# Sch.net
KiCad netlist of a schematic drawn in EAGLE
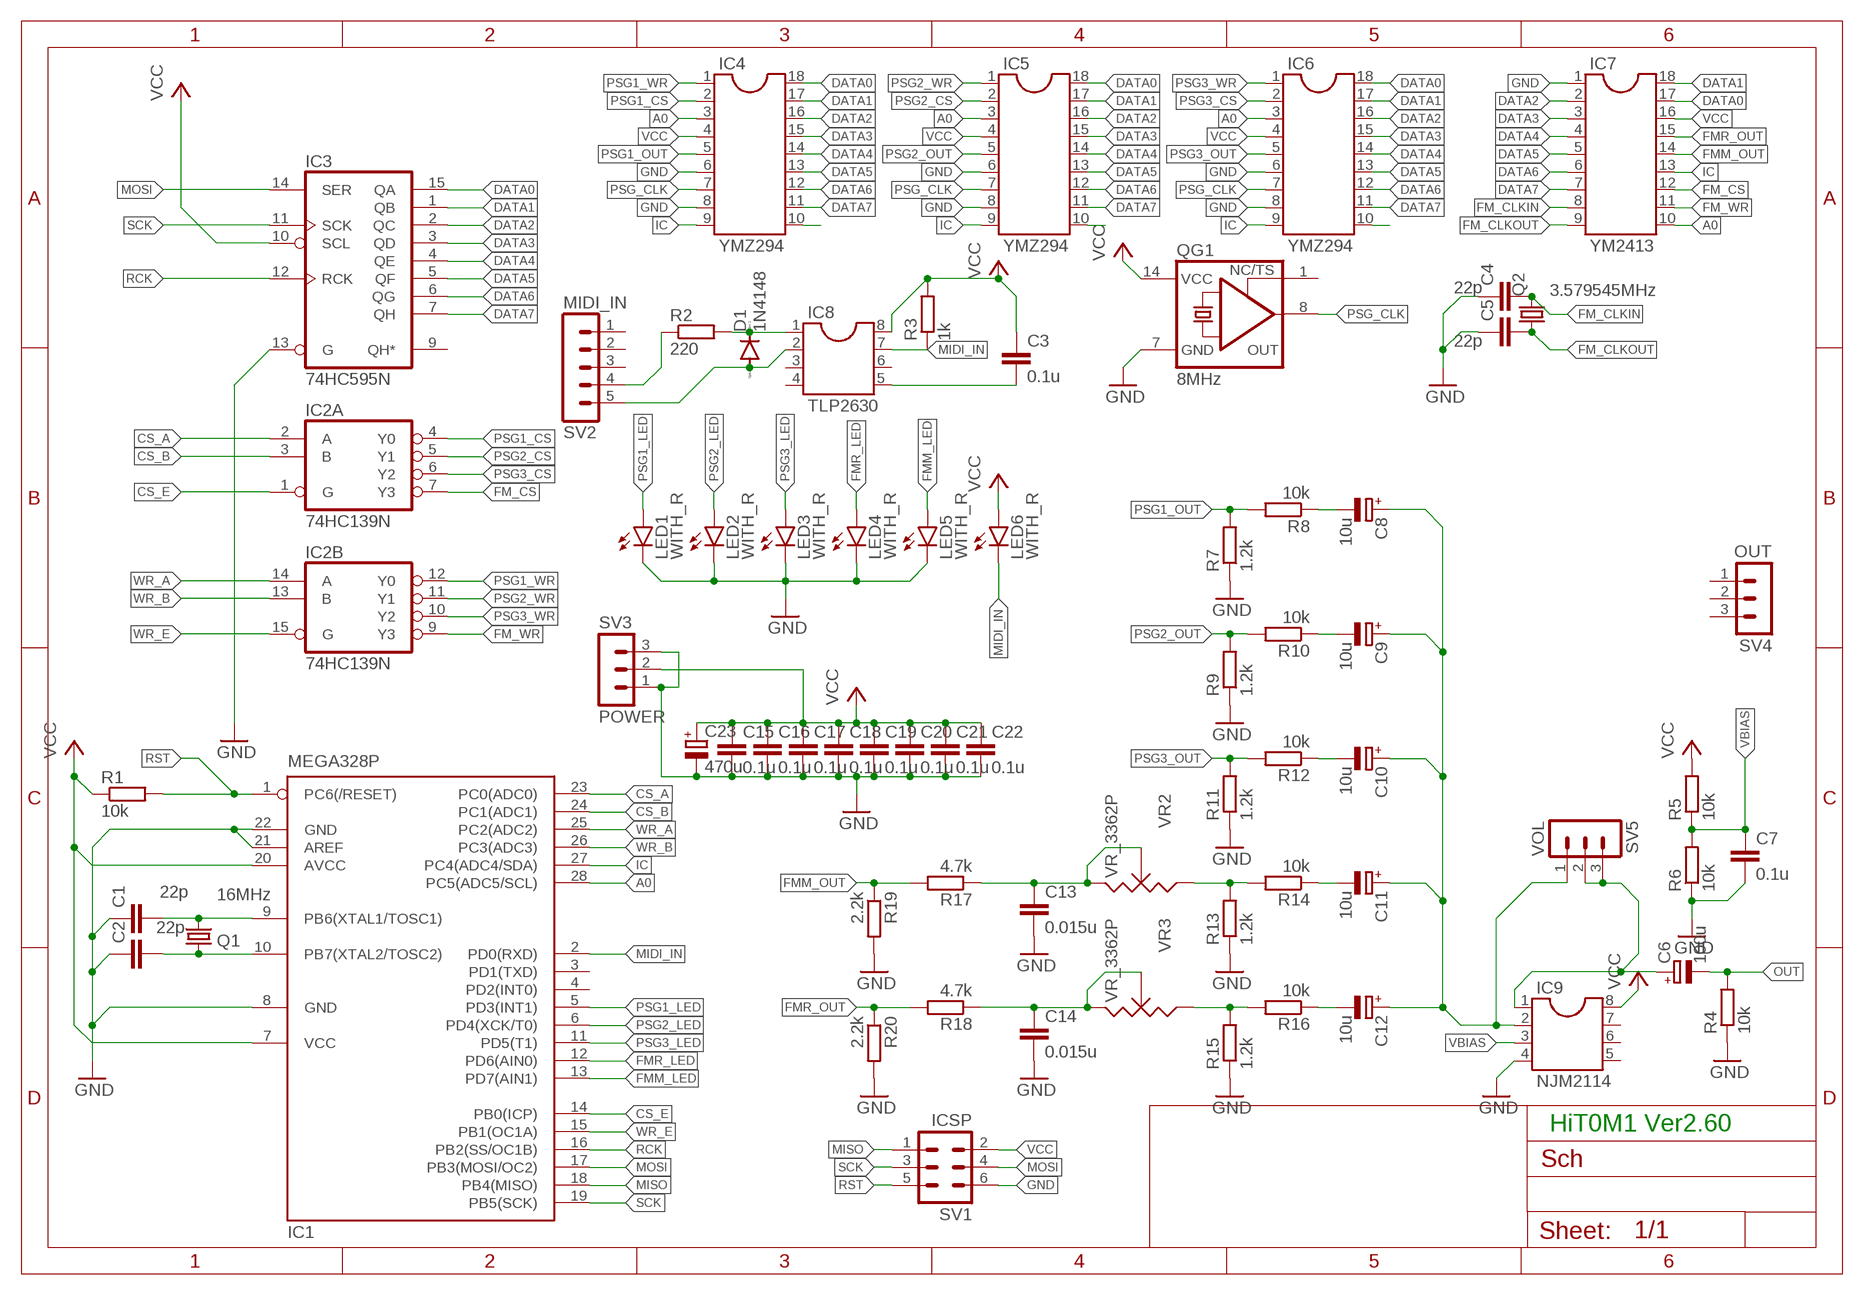
[diagram p0: schematic, sheet 1]

(export (version "E")
  (design (tool "Eeschema 10.0.6"))
  (components
    (comp (ref "C1")
      (value "22p")
      (footprint "eagle-import:C025-025X050")
      (libsource (lib "eagle-import") (part "C-EU025-025X050"))
    )
    (comp (ref "C2")
      (value "22p")
      (footprint "eagle-import:C025-025X050")
      (libsource (lib "eagle-import") (part "C-EU025-025X050"))
    )
    (comp (ref "C3")
      (value "0.1u")
      (footprint "eagle-import:C025-025X050")
      (libsource (lib "eagle-import") (part "C-EU025-025X050"))
    )
    (comp (ref "C4")
      (value "22p")
      (footprint "eagle-import:C025-025X050")
      (libsource (lib "eagle-import") (part "C-EU025-025X050"))
    )
    (comp (ref "C5")
      (value "22p")
      (footprint "eagle-import:C025-025X050")
      (libsource (lib "eagle-import") (part "C-EU025-025X050"))
    )
    (comp (ref "C6")
      (value "100u")
      (footprint "eagle-import:E2,5-6")
      (libsource (lib "eagle-import") (part "CPOL-EUE2.5-6"))
    )
    (comp (ref "C7")
      (value "0.1u")
      (footprint "eagle-import:C025-025X050")
      (libsource (lib "eagle-import") (part "C-EU025-025X050"))
    )
    (comp (ref "C8")
      (value "10u")
      (footprint "eagle-import:E2,5-6")
      (libsource (lib "eagle-import") (part "CPOL-EUE2.5-6"))
    )
    (comp (ref "C9")
      (value "10u")
      (footprint "eagle-import:E2,5-6")
      (libsource (lib "eagle-import") (part "CPOL-EUE2.5-6"))
    )
    (comp (ref "C10")
      (value "10u")
      (footprint "eagle-import:E2,5-6")
      (libsource (lib "eagle-import") (part "CPOL-EUE2.5-6"))
    )
    (comp (ref "C11")
      (value "10u")
      (footprint "eagle-import:E2,5-6")
      (libsource (lib "eagle-import") (part "CPOL-EUE2.5-6"))
    )
    (comp (ref "C12")
      (value "10u")
      (footprint "eagle-import:E2,5-6")
      (libsource (lib "eagle-import") (part "CPOL-EUE2.5-6"))
    )
    (comp (ref "C13")
      (value "0.015u")
      (footprint "eagle-import:C050-025X075")
      (libsource (lib "eagle-import") (part "C-EU050-025X075"))
    )
    (comp (ref "C14")
      (value "0.015u")
      (footprint "eagle-import:C050-025X075")
      (libsource (lib "eagle-import") (part "C-EU050-025X075"))
    )
    (comp (ref "C15")
      (value "0.1u")
      (footprint "eagle-import:C025-025X050")
      (libsource (lib "eagle-import") (part "C-EU025-025X050"))
    )
    (comp (ref "C16")
      (value "0.1u")
      (footprint "eagle-import:C025-025X050")
      (libsource (lib "eagle-import") (part "C-EU025-025X050"))
    )
    (comp (ref "C17")
      (value "0.1u")
      (footprint "eagle-import:C025-025X050")
      (libsource (lib "eagle-import") (part "C-EU025-025X050"))
    )
    (comp (ref "C18")
      (value "0.1u")
      (footprint "eagle-import:C025-025X050")
      (libsource (lib "eagle-import") (part "C-EU025-025X050"))
    )
    (comp (ref "C19")
      (value "0.1u")
      (footprint "eagle-import:C025-025X050")
      (libsource (lib "eagle-import") (part "C-EU025-025X050"))
    )
    (comp (ref "C20")
      (value "0.1u")
      (footprint "eagle-import:C025-025X050")
      (libsource (lib "eagle-import") (part "C-EU025-025X050"))
    )
    (comp (ref "C21")
      (value "0.1u")
      (footprint "eagle-import:C025-025X050")
      (libsource (lib "eagle-import") (part "C-EU025-025X050"))
    )
    (comp (ref "C22")
      (value "0.1u")
      (footprint "eagle-import:C025-025X050")
      (libsource (lib "eagle-import") (part "C-EU025-025X050"))
    )
    (comp (ref "C23")
      (value "470u")
      (footprint "eagle-import:E2,5-6")
      (libsource (lib "eagle-import") (part "CPOL-EUE2.5-6"))
    )
    (comp (ref "D1")
      (value "1N4148")
      (footprint "eagle-import:DO35-7")
      (libsource (lib "eagle-import") (part "1N4148DO35-7"))
    )
    (comp (ref "IC1")
      (value "MEGA328P")
      (footprint "eagle-import:DIL28-3")
      (libsource (lib "eagle-import") (part "MEGA8-P"))
    )
    (comp (ref "IC2")
      (value "74HC139N")
      (footprint "eagle-import:DIL16")
      (libsource (lib "eagle-import") (part "74139NHC"))
    )
    (comp (ref "IC3")
      (value "74HC595N")
      (footprint "eagle-import:DIL16")
      (libsource (lib "eagle-import") (part "74595NHC"))
    )
    (comp (ref "IC4")
      (value "YMZ294")
      (footprint "eagle-import:SOCKET-18")
      (libsource (lib "eagle-import") (part "DIL18S"))
    )
    (comp (ref "IC5")
      (value "YMZ294")
      (footprint "eagle-import:SOCKET-18")
      (libsource (lib "eagle-import") (part "DIL18S"))
    )
    (comp (ref "IC6")
      (value "YMZ294")
      (footprint "eagle-import:SOCKET-18")
      (libsource (lib "eagle-import") (part "DIL18S"))
    )
    (comp (ref "IC7")
      (value "YM2413")
      (footprint "eagle-import:SOCKET-18")
      (libsource (lib "eagle-import") (part "DIL18S"))
    )
    (comp (ref "IC8")
      (value "TLP2630")
      (footprint "eagle-import:SOCKET-08")
      (libsource (lib "eagle-import") (part "DIL8S"))
    )
    (comp (ref "IC9")
      (value "NJM2114")
      (footprint "eagle-import:SOCKET-08")
      (libsource (lib "eagle-import") (part "DIL8S"))
    )
    (comp (ref "LED1")
      (value "WITH_R")
      (footprint "eagle-import:LED3MM")
      (libsource (lib "eagle-import") (part "LED3MM"))
    )
    (comp (ref "LED2")
      (value "WITH_R")
      (footprint "eagle-import:LED3MM")
      (libsource (lib "eagle-import") (part "LED3MM"))
    )
    (comp (ref "LED3")
      (value "WITH_R")
      (footprint "eagle-import:LED3MM")
      (libsource (lib "eagle-import") (part "LED3MM"))
    )
    (comp (ref "LED4")
      (value "WITH_R")
      (footprint "eagle-import:LED3MM")
      (libsource (lib "eagle-import") (part "LED3MM"))
    )
    (comp (ref "LED5")
      (value "WITH_R")
      (footprint "eagle-import:LED3MM")
      (libsource (lib "eagle-import") (part "LED3MM"))
    )
    (comp (ref "LED6")
      (value "WITH_R")
      (footprint "eagle-import:LED3MM")
      (libsource (lib "eagle-import") (part "LED3MM"))
    )
    (comp (ref "Q1")
      (value "16MHz")
      (footprint "eagle-import:HC49_S")
      (libsource (lib "eagle-import") (part "CRYSTALHC49S"))
    )
    (comp (ref "Q2")
      (value "3.579545MHz")
      (footprint "eagle-import:HC49_S")
      (libsource (lib "eagle-import") (part "CRYSTALHC49S"))
    )
    (comp (ref "QG1")
      (value "8MHz")
      (footprint "eagle-import:DIL14S")
      (libsource (lib "eagle-import") (part "XO-14"))
    )
    (comp (ref "R1")
      (value "10k")
      (footprint "eagle-import:0207_10")
      (libsource (lib "eagle-import") (part "R-EU_0207/10"))
    )
    (comp (ref "R2")
      (value "220")
      (footprint "eagle-import:0207_10")
      (libsource (lib "eagle-import") (part "R-EU_0207/10"))
    )
    (comp (ref "R3")
      (value "1k")
      (footprint "eagle-import:0207_10")
      (libsource (lib "eagle-import") (part "R-EU_0207/10"))
    )
    (comp (ref "R4")
      (value "10k")
      (footprint "eagle-import:0207_10")
      (libsource (lib "eagle-import") (part "R-EU_0207/10"))
    )
    (comp (ref "R5")
      (value "10k")
      (footprint "eagle-import:0207_10")
      (libsource (lib "eagle-import") (part "R-EU_0207/10"))
    )
    (comp (ref "R6")
      (value "10k")
      (footprint "eagle-import:0207_10")
      (libsource (lib "eagle-import") (part "R-EU_0207/10"))
    )
    (comp (ref "R7")
      (value "1.2k")
      (footprint "eagle-import:0207_2V")
      (libsource (lib "eagle-import") (part "R-EU_0207/2V"))
    )
    (comp (ref "R8")
      (value "10k")
      (footprint "eagle-import:0207_2V")
      (libsource (lib "eagle-import") (part "R-EU_0207/2V"))
    )
    (comp (ref "R9")
      (value "1.2k")
      (footprint "eagle-import:0207_2V")
      (libsource (lib "eagle-import") (part "R-EU_0207/2V"))
    )
    (comp (ref "R10")
      (value "10k")
      (footprint "eagle-import:0207_2V")
      (libsource (lib "eagle-import") (part "R-EU_0207/2V"))
    )
    (comp (ref "R11")
      (value "1.2k")
      (footprint "eagle-import:0207_2V")
      (libsource (lib "eagle-import") (part "R-EU_0207/2V"))
    )
    (comp (ref "R12")
      (value "10k")
      (footprint "eagle-import:0207_2V")
      (libsource (lib "eagle-import") (part "R-EU_0207/2V"))
    )
    (comp (ref "R13")
      (value "1.2k")
      (footprint "eagle-import:0207_2V")
      (libsource (lib "eagle-import") (part "R-EU_0207/2V"))
    )
    (comp (ref "R14")
      (value "10k")
      (footprint "eagle-import:0207_2V")
      (libsource (lib "eagle-import") (part "R-EU_0207/2V"))
    )
    (comp (ref "R15")
      (value "1.2k")
      (footprint "eagle-import:0207_2V")
      (libsource (lib "eagle-import") (part "R-EU_0207/2V"))
    )
    (comp (ref "R16")
      (value "10k")
      (footprint "eagle-import:0207_2V")
      (libsource (lib "eagle-import") (part "R-EU_0207/2V"))
    )
    (comp (ref "R17")
      (value "4.7k")
      (footprint "eagle-import:0207_2V")
      (libsource (lib "eagle-import") (part "R-EU_0207/2V"))
    )
    (comp (ref "R18")
      (value "4.7k")
      (footprint "eagle-import:0207_2V")
      (libsource (lib "eagle-import") (part "R-EU_0207/2V"))
    )
    (comp (ref "R19")
      (value "2.2k")
      (footprint "eagle-import:0207_2V")
      (libsource (lib "eagle-import") (part "R-EU_0207/2V"))
    )
    (comp (ref "R20")
      (value "2.2k")
      (footprint "eagle-import:0207_2V")
      (libsource (lib "eagle-import") (part "R-EU_0207/2V"))
    )
    (comp (ref "SV1")
      (value "ICSP")
      (footprint "eagle-import:MA03-2")
      (libsource (lib "eagle-import") (part "MA03-2"))
    )
    (comp (ref "SV2")
      (value "MIDI_IN")
      (footprint "eagle-import:MA05-1")
      (libsource (lib "eagle-import") (part "MA05-1"))
    )
    (comp (ref "SV3")
      (value "POWER")
      (footprint "eagle-import:MA03-1")
      (libsource (lib "eagle-import") (part "MA03-1"))
    )
    (comp (ref "SV4")
      (value "OUT")
      (footprint "eagle-import:MA03-1")
      (libsource (lib "eagle-import") (part "MA03-1"))
    )
    (comp (ref "SV5")
      (value "VOL")
      (footprint "eagle-import:MA03-1")
      (libsource (lib "eagle-import") (part "MA03-1"))
    )
    (comp (ref "VR2")
      (value "VR_3362P")
      (footprint "eagle-import:VR_3362P")
      (libsource (lib "eagle-import") (part "P-03277_VR_3362P"))
    )
    (comp (ref "VR3")
      (value "VR_3362P")
      (footprint "eagle-import:VR_3362P")
      (libsource (lib "eagle-import") (part "P-03277_VR_3362P"))
    )
  )
  (nets
    (net (code "1") (name "A0") (class "Default")
      (node (ref "IC1") (pin "28") (pinfunction "PC5(ADC5/SCL)_28") (pintype "bidirectional"))
      (node (ref "IC4") (pin "3") (pinfunction "3_3") (pintype "passive"))
      (node (ref "IC5") (pin "3") (pinfunction "3_3") (pintype "passive"))
      (node (ref "IC6") (pin "3") (pinfunction "3_3") (pintype "passive"))
      (node (ref "IC7") (pin "10") (pinfunction "10_10") (pintype "passive"))
    )
    (net (code "2") (name "CS_A") (class "Default")
      (node (ref "IC1") (pin "23") (pinfunction "PC0(ADC0)_23") (pintype "bidirectional"))
      (node (ref "IC2") (pin "2") (pinfunction "A_2") (pintype "input"))
    )
    (net (code "3") (name "CS_B") (class "Default")
      (node (ref "IC1") (pin "24") (pinfunction "PC1(ADC1)_24") (pintype "bidirectional"))
      (node (ref "IC2") (pin "3") (pinfunction "B_3") (pintype "input"))
    )
    (net (code "4") (name "CS_E") (class "Default")
      (node (ref "IC1") (pin "14") (pinfunction "PB0(ICP)_14") (pintype "bidirectional"))
      (node (ref "IC2") (pin "1") (pinfunction "G_1") (pintype "input"))
    )
    (net (code "5") (name "DATA0") (class "Default")
      (node (ref "IC3") (pin "15") (pinfunction "QA_15") (pintype "tri_state"))
      (node (ref "IC4") (pin "18") (pinfunction "18_18") (pintype "passive"))
      (node (ref "IC5") (pin "18") (pinfunction "18_18") (pintype "passive"))
      (node (ref "IC6") (pin "18") (pinfunction "18_18") (pintype "passive"))
      (node (ref "IC7") (pin "17") (pinfunction "17_17") (pintype "passive"))
    )
    (net (code "6") (name "DATA1") (class "Default")
      (node (ref "IC3") (pin "1") (pinfunction "QB_1") (pintype "tri_state"))
      (node (ref "IC4") (pin "17") (pinfunction "17_17") (pintype "passive"))
      (node (ref "IC5") (pin "17") (pinfunction "17_17") (pintype "passive"))
      (node (ref "IC6") (pin "17") (pinfunction "17_17") (pintype "passive"))
      (node (ref "IC7") (pin "18") (pinfunction "18_18") (pintype "passive"))
    )
    (net (code "7") (name "DATA2") (class "Default")
      (node (ref "IC3") (pin "2") (pinfunction "QC_2") (pintype "tri_state"))
      (node (ref "IC4") (pin "16") (pinfunction "16_16") (pintype "passive"))
      (node (ref "IC5") (pin "16") (pinfunction "16_16") (pintype "passive"))
      (node (ref "IC6") (pin "16") (pinfunction "16_16") (pintype "passive"))
      (node (ref "IC7") (pin "2") (pinfunction "2_2") (pintype "passive"))
    )
    (net (code "8") (name "DATA3") (class "Default")
      (node (ref "IC3") (pin "3") (pinfunction "QD_3") (pintype "tri_state"))
      (node (ref "IC4") (pin "15") (pinfunction "15_15") (pintype "passive"))
      (node (ref "IC5") (pin "15") (pinfunction "15_15") (pintype "passive"))
      (node (ref "IC6") (pin "15") (pinfunction "15_15") (pintype "passive"))
      (node (ref "IC7") (pin "3") (pinfunction "3_3") (pintype "passive"))
    )
    (net (code "9") (name "DATA4") (class "Default")
      (node (ref "IC3") (pin "4") (pinfunction "QE_4") (pintype "tri_state"))
      (node (ref "IC4") (pin "14") (pinfunction "14_14") (pintype "passive"))
      (node (ref "IC5") (pin "14") (pinfunction "14_14") (pintype "passive"))
      (node (ref "IC6") (pin "14") (pinfunction "14_14") (pintype "passive"))
      (node (ref "IC7") (pin "4") (pinfunction "4_4") (pintype "passive"))
    )
    (net (code "10") (name "DATA5") (class "Default")
      (node (ref "IC3") (pin "5") (pinfunction "QF_5") (pintype "tri_state"))
      (node (ref "IC4") (pin "13") (pinfunction "13_13") (pintype "passive"))
      (node (ref "IC5") (pin "13") (pinfunction "13_13") (pintype "passive"))
      (node (ref "IC6") (pin "13") (pinfunction "13_13") (pintype "passive"))
      (node (ref "IC7") (pin "5") (pinfunction "5_5") (pintype "passive"))
    )
    (net (code "11") (name "DATA6") (class "Default")
      (node (ref "IC3") (pin "6") (pinfunction "QG_6") (pintype "tri_state"))
      (node (ref "IC4") (pin "12") (pinfunction "12_12") (pintype "passive"))
      (node (ref "IC5") (pin "12") (pinfunction "12_12") (pintype "passive"))
      (node (ref "IC6") (pin "12") (pinfunction "12_12") (pintype "passive"))
      (node (ref "IC7") (pin "6") (pinfunction "6_6") (pintype "passive"))
    )
    (net (code "12") (name "DATA7") (class "Default")
      (node (ref "IC3") (pin "7") (pinfunction "QH_7") (pintype "tri_state"))
      (node (ref "IC4") (pin "11") (pinfunction "11_11") (pintype "passive"))
      (node (ref "IC5") (pin "11") (pinfunction "11_11") (pintype "passive"))
      (node (ref "IC6") (pin "11") (pinfunction "11_11") (pintype "passive"))
      (node (ref "IC7") (pin "7") (pinfunction "7_7") (pintype "passive"))
    )
    (net (code "13") (name "FMM_LED") (class "Default")
      (node (ref "IC1") (pin "13") (pinfunction "PD7(AIN1)_13") (pintype "bidirectional"))
      (node (ref "LED5") (pin "A") (pinfunction "A_A") (pintype "passive"))
    )
    (net (code "14") (name "FMM_OUT") (class "Default")
      (node (ref "IC7") (pin "14") (pinfunction "14_14") (pintype "passive"))
      (node (ref "R17") (pin "2") (pinfunction "2_2") (pintype "passive"))
      (node (ref "R19") (pin "1") (pinfunction "1_1") (pintype "passive"))
    )
    (net (code "15") (name "FMR_LED") (class "Default")
      (node (ref "IC1") (pin "12") (pinfunction "PD6(AIN0)_12") (pintype "bidirectional"))
      (node (ref "LED4") (pin "A") (pinfunction "A_A") (pintype "passive"))
    )
    (net (code "16") (name "FMR_OUT") (class "Default")
      (node (ref "IC7") (pin "15") (pinfunction "15_15") (pintype "passive"))
      (node (ref "R18") (pin "2") (pinfunction "2_2") (pintype "passive"))
      (node (ref "R20") (pin "1") (pinfunction "1_1") (pintype "passive"))
    )
    (net (code "17") (name "FM_CLKIN") (class "Default")
      (node (ref "C4") (pin "2") (pinfunction "2_2") (pintype "passive"))
      (node (ref "IC7") (pin "8") (pinfunction "8_8") (pintype "passive"))
      (node (ref "Q2") (pin "2") (pinfunction "2_2") (pintype "passive"))
    )
    (net (code "18") (name "FM_CLKOUT") (class "Default")
      (node (ref "C5") (pin "2") (pinfunction "2_2") (pintype "passive"))
      (node (ref "IC7") (pin "9") (pinfunction "9_9") (pintype "passive"))
      (node (ref "Q2") (pin "1") (pinfunction "1_1") (pintype "passive"))
    )
    (net (code "19") (name "FM_CS") (class "Default")
      (node (ref "IC2") (pin "7") (pinfunction "Y3_7") (pintype "output"))
      (node (ref "IC7") (pin "12") (pinfunction "12_12") (pintype "passive"))
    )
    (net (code "20") (name "FM_WR") (class "Default")
      (node (ref "IC2") (pin "9") (pinfunction "Y3_9") (pintype "output"))
      (node (ref "IC7") (pin "11") (pinfunction "11_11") (pintype "passive"))
    )
    (net (code "21") (name "GND") (class "Default")
      (node (ref "C1") (pin "1") (pinfunction "1_1") (pintype "passive"))
      (node (ref "C13") (pin "2") (pinfunction "2_2") (pintype "passive"))
      (node (ref "C14") (pin "2") (pinfunction "2_2") (pintype "passive"))
      (node (ref "C15") (pin "2") (pinfunction "2_2") (pintype "passive"))
      (node (ref "C16") (pin "2") (pinfunction "2_2") (pintype "passive"))
      (node (ref "C17") (pin "2") (pinfunction "2_2") (pintype "passive"))
      (node (ref "C18") (pin "2") (pinfunction "2_2") (pintype "passive"))
      (node (ref "C19") (pin "2") (pinfunction "2_2") (pintype "passive"))
      (node (ref "C2") (pin "1") (pinfunction "1_1") (pintype "passive"))
      (node (ref "C20") (pin "2") (pinfunction "2_2") (pintype "passive"))
      (node (ref "C21") (pin "2") (pinfunction "2_2") (pintype "passive"))
      (node (ref "C22") (pin "2") (pinfunction "2_2") (pintype "passive"))
      (node (ref "C23") (pin "-") (pinfunction "-_-") (pintype "passive"))
      (node (ref "C4") (pin "1") (pinfunction "1_1") (pintype "passive"))
      (node (ref "C5") (pin "1") (pinfunction "1_1") (pintype "passive"))
      (node (ref "C7") (pin "2") (pinfunction "2_2") (pintype "passive"))
      (node (ref "IC1") (pin "21") (pinfunction "AREF_21") (pintype "passive"))
      (node (ref "IC1") (pin "22") (pinfunction "GND_22") (pintype "power_in"))
      (node (ref "IC1") (pin "8") (pinfunction "GND_8") (pintype "power_in"))
      (node (ref "IC3") (pin "13") (pinfunction "G_13") (pintype "input"))
      (node (ref "IC4") (pin "6") (pinfunction "6_6") (pintype "passive"))
      (node (ref "IC4") (pin "8") (pinfunction "8_8") (pintype "passive"))
      (node (ref "IC5") (pin "6") (pinfunction "6_6") (pintype "passive"))
      (node (ref "IC5") (pin "8") (pinfunction "8_8") (pintype "passive"))
      (node (ref "IC6") (pin "6") (pinfunction "6_6") (pintype "passive"))
      (node (ref "IC6") (pin "8") (pinfunction "8_8") (pintype "passive"))
      (node (ref "IC7") (pin "1") (pinfunction "1_1") (pintype "passive"))
      (node (ref "IC9") (pin "4") (pinfunction "4_4") (pintype "passive"))
      (node (ref "LED1") (pin "K") (pinfunction "C_K") (pintype "passive"))
      (node (ref "LED2") (pin "K") (pinfunction "C_K") (pintype "passive"))
      (node (ref "LED3") (pin "K") (pinfunction "C_K") (pintype "passive"))
      (node (ref "LED4") (pin "K") (pinfunction "C_K") (pintype "passive"))
      (node (ref "LED5") (pin "K") (pinfunction "C_K") (pintype "passive"))
      (node (ref "QG1") (pin "7") (pinfunction "GND_7") (pintype "power_in"))
      (node (ref "R11") (pin "1") (pinfunction "1_1") (pintype "passive"))
      (node (ref "R13") (pin "1") (pinfunction "1_1") (pintype "passive"))
      (node (ref "R15") (pin "1") (pinfunction "1_1") (pintype "passive"))
      (node (ref "R19") (pin "2") (pinfunction "2_2") (pintype "passive"))
      (node (ref "R20") (pin "2") (pinfunction "2_2") (pintype "passive"))
      (node (ref "R4") (pin "1") (pinfunction "1_1") (pintype "passive"))
      (node (ref "R6") (pin "1") (pinfunction "1_1") (pintype "passive"))
      (node (ref "R7") (pin "1") (pinfunction "1_1") (pintype "passive"))
      (node (ref "R9") (pin "1") (pinfunction "1_1") (pintype "passive"))
      (node (ref "SV1") (pin "6") (pinfunction "6_6") (pintype "passive"))
      (node (ref "SV3") (pin "1") (pinfunction "1_1") (pintype "passive"))
      (node (ref "SV3") (pin "3") (pinfunction "3_3") (pintype "passive"))
    )
    (net (code "22") (name "IC") (class "Default")
      (node (ref "IC1") (pin "27") (pinfunction "PC4(ADC4/SDA)_27") (pintype "bidirectional"))
      (node (ref "IC4") (pin "9") (pinfunction "9_9") (pintype "passive"))
      (node (ref "IC5") (pin "9") (pinfunction "9_9") (pintype "passive"))
      (node (ref "IC6") (pin "9") (pinfunction "9_9") (pintype "passive"))
      (node (ref "IC7") (pin "13") (pinfunction "13_13") (pintype "passive"))
    )
    (net (code "23") (name "MIDI_IN") (class "Default")
      (node (ref "IC1") (pin "2") (pinfunction "PD0(RXD)_2") (pintype "bidirectional"))
      (node (ref "IC8") (pin "7") (pinfunction "7_7") (pintype "passive"))
      (node (ref "LED6") (pin "K") (pinfunction "C_K") (pintype "passive"))
      (node (ref "R3") (pin "1") (pinfunction "1_1") (pintype "passive"))
    )
    (net (code "24") (name "MISO") (class "Default")
      (node (ref "IC1") (pin "18") (pinfunction "PB4(MISO)_18") (pintype "bidirectional"))
      (node (ref "SV1") (pin "1") (pinfunction "1_1") (pintype "passive"))
    )
    (net (code "25") (name "MOSI") (class "Default")
      (node (ref "IC1") (pin "17") (pinfunction "PB3(MOSI/OC2)_17") (pintype "bidirectional"))
      (node (ref "IC3") (pin "14") (pinfunction "SER_14") (pintype "input"))
      (node (ref "SV1") (pin "4") (pinfunction "4_4") (pintype "passive"))
    )
    (net (code "26") (name "Net-(C3-Pad2)") (class "Default")
      (node (ref "C3") (pin "2") (pinfunction "2_2") (pintype "passive"))
      (node (ref "IC8") (pin "5") (pinfunction "5_5") (pintype "passive"))
    )
    (net (code "27") (name "Net-(C6-Pad+)") (class "Default")
      (node (ref "C6") (pin "+") (pinfunction "+_+") (pintype "passive"))
      (node (ref "IC9") (pin "1") (pinfunction "1_1") (pintype "passive"))
      (node (ref "SV5") (pin "2") (pinfunction "2_2") (pintype "passive"))
      (node (ref "SV5") (pin "3") (pinfunction "3_3") (pintype "passive"))
    )
    (net (code "28") (name "Net-(C8-Pad-)") (class "Default")
      (node (ref "C8") (pin "-") (pinfunction "-_-") (pintype "passive"))
      (node (ref "R8") (pin "1") (pinfunction "1_1") (pintype "passive"))
    )
    (net (code "29") (name "Net-(C9-Pad-)") (class "Default")
      (node (ref "C9") (pin "-") (pinfunction "-_-") (pintype "passive"))
      (node (ref "R10") (pin "1") (pinfunction "1_1") (pintype "passive"))
    )
    (net (code "30") (name "Net-(C10-Pad+)") (class "Default")
      (node (ref "C10") (pin "+") (pinfunction "+_+") (pintype "passive"))
      (node (ref "C11") (pin "+") (pinfunction "+_+") (pintype "passive"))
      (node (ref "C12") (pin "+") (pinfunction "+_+") (pintype "passive"))
      (node (ref "C8") (pin "+") (pinfunction "+_+") (pintype "passive"))
      (node (ref "C9") (pin "+") (pinfunction "+_+") (pintype "passive"))
      (node (ref "IC9") (pin "2") (pinfunction "2_2") (pintype "passive"))
      (node (ref "SV5") (pin "1") (pinfunction "1_1") (pintype "passive"))
    )
    (net (code "31") (name "Net-(C10-Pad-)") (class "Default")
      (node (ref "C10") (pin "-") (pinfunction "-_-") (pintype "passive"))
      (node (ref "R12") (pin "1") (pinfunction "1_1") (pintype "passive"))
    )
    (net (code "32") (name "Net-(C11-Pad-)") (class "Default")
      (node (ref "C11") (pin "-") (pinfunction "-_-") (pintype "passive"))
      (node (ref "R14") (pin "1") (pinfunction "1_1") (pintype "passive"))
    )
    (net (code "33") (name "Net-(C12-Pad-)") (class "Default")
      (node (ref "C12") (pin "-") (pinfunction "-_-") (pintype "passive"))
      (node (ref "R16") (pin "1") (pinfunction "1_1") (pintype "passive"))
    )
    (net (code "34") (name "Net-(C13-Pad1)") (class "Default")
      (node (ref "C13") (pin "1") (pinfunction "1_1") (pintype "passive"))
      (node (ref "R17") (pin "1") (pinfunction "1_1") (pintype "passive"))
      (node (ref "VR2") (pin "2") (pinfunction "2_2") (pintype "bidirectional"))
      (node (ref "VR2") (pin "3") (pinfunction "3_3") (pintype "bidirectional"))
    )
    (net (code "35") (name "Net-(C14-Pad1)") (class "Default")
      (node (ref "C14") (pin "1") (pinfunction "1_1") (pintype "passive"))
      (node (ref "R18") (pin "1") (pinfunction "1_1") (pintype "passive"))
      (node (ref "VR3") (pin "2") (pinfunction "2_2") (pintype "bidirectional"))
      (node (ref "VR3") (pin "3") (pinfunction "3_3") (pintype "bidirectional"))
    )
    (net (code "36") (name "Net-(D1-PadA)") (class "Default")
      (node (ref "D1") (pin "A") (pinfunction "A_A") (pintype "passive"))
      (node (ref "IC8") (pin "2") (pinfunction "2_2") (pintype "passive"))
      (node (ref "SV2") (pin "5") (pinfunction "5_5") (pintype "passive"))
    )
    (net (code "37") (name "Net-(D1-PadC)") (class "Default")
      (node (ref "D1") (pin "C") (pinfunction "C_C") (pintype "passive"))
      (node (ref "IC8") (pin "1") (pinfunction "1_1") (pintype "passive"))
      (node (ref "R2") (pin "2") (pinfunction "2_2") (pintype "passive"))
    )
    (net (code "38") (name "Net-(IC1-PB6(XTAL1{slash}TOSC1))") (class "Default")
      (node (ref "C1") (pin "2") (pinfunction "2_2") (pintype "passive"))
      (node (ref "IC1") (pin "9") (pinfunction "PB6(XTAL1/TOSC1)_9") (pintype "bidirectional"))
      (node (ref "Q1") (pin "2") (pinfunction "2_2") (pintype "passive"))
    )
    (net (code "39") (name "Net-(IC1-PB7(XTAL2{slash}TOSC2))") (class "Default")
      (node (ref "C2") (pin "2") (pinfunction "2_2") (pintype "passive"))
      (node (ref "IC1") (pin "10") (pinfunction "PB7(XTAL2/TOSC2)_10") (pintype "bidirectional"))
      (node (ref "Q1") (pin "1") (pinfunction "1_1") (pintype "passive"))
    )
    (net (code "40") (name "Net-(R2-Pad1)") (class "Default")
      (node (ref "R2") (pin "1") (pinfunction "1_1") (pintype "passive"))
      (node (ref "SV2") (pin "4") (pinfunction "4_4") (pintype "passive"))
    )
    (net (code "41") (name "Net-(R13-Pad2)") (class "Default")
      (node (ref "R13") (pin "2") (pinfunction "2_2") (pintype "passive"))
      (node (ref "R14") (pin "2") (pinfunction "2_2") (pintype "passive"))
      (node (ref "VR2") (pin "1") (pinfunction "1_1") (pintype "bidirectional"))
    )
    (net (code "42") (name "Net-(R15-Pad2)") (class "Default")
      (node (ref "R15") (pin "2") (pinfunction "2_2") (pintype "passive"))
      (node (ref "R16") (pin "2") (pinfunction "2_2") (pintype "passive"))
      (node (ref "VR3") (pin "1") (pinfunction "1_1") (pintype "bidirectional"))
    )
    (net (code "43") (name "OUT") (class "Default")
      (node (ref "C6") (pin "-") (pinfunction "-_-") (pintype "passive"))
      (node (ref "R4") (pin "2") (pinfunction "2_2") (pintype "passive"))
    )
    (net (code "44") (name "PSG1_CS") (class "Default")
      (node (ref "IC2") (pin "4") (pinfunction "Y0_4") (pintype "output"))
      (node (ref "IC4") (pin "2") (pinfunction "2_2") (pintype "passive"))
    )
    (net (code "45") (name "PSG1_LED") (class "Default")
      (node (ref "IC1") (pin "5") (pinfunction "PD3(INT1)_5") (pintype "bidirectional"))
      (node (ref "LED1") (pin "A") (pinfunction "A_A") (pintype "passive"))
    )
    (net (code "46") (name "PSG1_OUT") (class "Default")
      (node (ref "IC4") (pin "5") (pinfunction "5_5") (pintype "passive"))
      (node (ref "R7") (pin "2") (pinfunction "2_2") (pintype "passive"))
      (node (ref "R8") (pin "2") (pinfunction "2_2") (pintype "passive"))
    )
    (net (code "47") (name "PSG1_WR") (class "Default")
      (node (ref "IC2") (pin "12") (pinfunction "Y0_12") (pintype "output"))
      (node (ref "IC4") (pin "1") (pinfunction "1_1") (pintype "passive"))
    )
    (net (code "48") (name "PSG2_CS") (class "Default")
      (node (ref "IC2") (pin "5") (pinfunction "Y1_5") (pintype "output"))
      (node (ref "IC5") (pin "2") (pinfunction "2_2") (pintype "passive"))
    )
    (net (code "49") (name "PSG2_LED") (class "Default")
      (node (ref "IC1") (pin "6") (pinfunction "PD4(XCK/T0)_6") (pintype "bidirectional"))
      (node (ref "LED2") (pin "A") (pinfunction "A_A") (pintype "passive"))
    )
    (net (code "50") (name "PSG2_OUT") (class "Default")
      (node (ref "IC5") (pin "5") (pinfunction "5_5") (pintype "passive"))
      (node (ref "R10") (pin "2") (pinfunction "2_2") (pintype "passive"))
      (node (ref "R9") (pin "2") (pinfunction "2_2") (pintype "passive"))
    )
    (net (code "51") (name "PSG2_WR") (class "Default")
      (node (ref "IC2") (pin "11") (pinfunction "Y1_11") (pintype "output"))
      (node (ref "IC5") (pin "1") (pinfunction "1_1") (pintype "passive"))
    )
    (net (code "52") (name "PSG3_CS") (class "Default")
      (node (ref "IC2") (pin "6") (pinfunction "Y2_6") (pintype "output"))
      (node (ref "IC6") (pin "2") (pinfunction "2_2") (pintype "passive"))
    )
    (net (code "53") (name "PSG3_LED") (class "Default")
      (node (ref "IC1") (pin "11") (pinfunction "PD5(T1)_11") (pintype "bidirectional"))
      (node (ref "LED3") (pin "A") (pinfunction "A_A") (pintype "passive"))
    )
    (net (code "54") (name "PSG3_OUT") (class "Default")
      (node (ref "IC6") (pin "5") (pinfunction "5_5") (pintype "passive"))
      (node (ref "R11") (pin "2") (pinfunction "2_2") (pintype "passive"))
      (node (ref "R12") (pin "2") (pinfunction "2_2") (pintype "passive"))
    )
    (net (code "55") (name "PSG3_WR") (class "Default")
      (node (ref "IC2") (pin "10") (pinfunction "Y2_10") (pintype "output"))
      (node (ref "IC6") (pin "1") (pinfunction "1_1") (pintype "passive"))
    )
    (net (code "56") (name "PSG_CLK") (class "Default")
      (node (ref "IC4") (pin "7") (pinfunction "7_7") (pintype "passive"))
      (node (ref "IC5") (pin "7") (pinfunction "7_7") (pintype "passive"))
      (node (ref "IC6") (pin "7") (pinfunction "7_7") (pintype "passive"))
      (node (ref "QG1") (pin "8") (pinfunction "OUT_8") (pintype "output"))
    )
    (net (code "57") (name "RCK") (class "Default")
      (node (ref "IC1") (pin "16") (pinfunction "PB2(SS/OC1B)_16") (pintype "bidirectional"))
      (node (ref "IC3") (pin "12") (pinfunction "RCK_12") (pintype "input"))
    )
    (net (code "58") (name "RST") (class "Default")
      (node (ref "IC1") (pin "1") (pinfunction "PC6(/RESET)_1") (pintype "bidirectional"))
      (node (ref "R1") (pin "2") (pinfunction "2_2") (pintype "passive"))
      (node (ref "SV1") (pin "5") (pinfunction "5_5") (pintype "passive"))
    )
    (net (code "59") (name "SCK") (class "Default")
      (node (ref "IC1") (pin "19") (pinfunction "PB5(SCK)_19") (pintype "bidirectional"))
      (node (ref "IC3") (pin "11") (pinfunction "SCK_11") (pintype "input"))
      (node (ref "SV1") (pin "3") (pinfunction "3_3") (pintype "passive"))
    )
    (net (code "60") (name "VBIAS") (class "Default")
      (node (ref "C7") (pin "1") (pinfunction "1_1") (pintype "passive"))
      (node (ref "IC9") (pin "3") (pinfunction "3_3") (pintype "passive"))
      (node (ref "R5") (pin "1") (pinfunction "1_1") (pintype "passive"))
      (node (ref "R6") (pin "2") (pinfunction "2_2") (pintype "passive"))
    )
    (net (code "61") (name "VCC") (class "Default")
      (node (ref "C15") (pin "1") (pinfunction "1_1") (pintype "passive"))
      (node (ref "C16") (pin "1") (pinfunction "1_1") (pintype "passive"))
      (node (ref "C17") (pin "1") (pinfunction "1_1") (pintype "passive"))
      (node (ref "C18") (pin "1") (pinfunction "1_1") (pintype "passive"))
      (node (ref "C19") (pin "1") (pinfunction "1_1") (pintype "passive"))
      (node (ref "C20") (pin "1") (pinfunction "1_1") (pintype "passive"))
      (node (ref "C21") (pin "1") (pinfunction "1_1") (pintype "passive"))
      (node (ref "C22") (pin "1") (pinfunction "1_1") (pintype "passive"))
      (node (ref "C23") (pin "+") (pinfunction "+_+") (pintype "passive"))
      (node (ref "C3") (pin "1") (pinfunction "1_1") (pintype "passive"))
      (node (ref "IC1") (pin "20") (pinfunction "AVCC_20") (pintype "power_in"))
      (node (ref "IC1") (pin "7") (pinfunction "VCC_7") (pintype "power_in"))
      (node (ref "IC3") (pin "10") (pinfunction "SCL_10") (pintype "input"))
      (node (ref "IC4") (pin "4") (pinfunction "4_4") (pintype "passive"))
      (node (ref "IC5") (pin "4") (pinfunction "4_4") (pintype "passive"))
      (node (ref "IC6") (pin "4") (pinfunction "4_4") (pintype "passive"))
      (node (ref "IC7") (pin "16") (pinfunction "16_16") (pintype "passive"))
      (node (ref "IC8") (pin "8") (pinfunction "8_8") (pintype "passive"))
      (node (ref "IC9") (pin "8") (pinfunction "8_8") (pintype "passive"))
      (node (ref "LED6") (pin "A") (pinfunction "A_A") (pintype "passive"))
      (node (ref "QG1") (pin "14") (pinfunction "VCC_14") (pintype "power_in"))
      (node (ref "R1") (pin "1") (pinfunction "1_1") (pintype "passive"))
      (node (ref "R3") (pin "2") (pinfunction "2_2") (pintype "passive"))
      (node (ref "R5") (pin "2") (pinfunction "2_2") (pintype "passive"))
      (node (ref "SV1") (pin "2") (pinfunction "2_2") (pintype "passive"))
      (node (ref "SV3") (pin "2") (pinfunction "2_2") (pintype "passive"))
    )
    (net (code "62") (name "WR_A") (class "Default")
      (node (ref "IC1") (pin "25") (pinfunction "PC2(ADC2)_25") (pintype "bidirectional"))
      (node (ref "IC2") (pin "14") (pinfunction "A_14") (pintype "input"))
    )
    (net (code "63") (name "WR_B") (class "Default")
      (node (ref "IC1") (pin "26") (pinfunction "PC3(ADC3)_26") (pintype "bidirectional"))
      (node (ref "IC2") (pin "13") (pinfunction "B_13") (pintype "input"))
    )
    (net (code "64") (name "WR_E") (class "Default")
      (node (ref "IC1") (pin "15") (pinfunction "PB1(OC1A)_15") (pintype "bidirectional"))
      (node (ref "IC2") (pin "15") (pinfunction "G_15") (pintype "input"))
    )
    (net (code "65") (name "unconnected-(IC1-PD1(TXD)-Pad3)") (class "Default")
      (node (ref "IC1") (pin "3") (pinfunction "PD1(TXD)_3") (pintype "bidirectional"))
    )
    (net (code "66") (name "unconnected-(IC1-PD2(INT0)-Pad4)") (class "Default")
      (node (ref "IC1") (pin "4") (pinfunction "PD2(INT0)_4") (pintype "bidirectional"))
    )
    (net (code "67") (name "unconnected-(IC3A-QH*-Pad9)") (class "Default")
      (node (ref "IC3") (pin "9") (pinfunction "QH*_9") (pintype "tri_state"))
    )
    (net (code "68") (name "unconnected-(IC4-Pad10)") (class "Default")
      (node (ref "IC4") (pin "10") (pinfunction "10_10") (pintype "passive"))
    )
    (net (code "69") (name "unconnected-(IC5-Pad10)") (class "Default")
      (node (ref "IC5") (pin "10") (pinfunction "10_10") (pintype "passive"))
    )
    (net (code "70") (name "unconnected-(IC6-Pad10)") (class "Default")
      (node (ref "IC6") (pin "10") (pinfunction "10_10") (pintype "passive"))
    )
    (net (code "71") (name "unconnected-(IC8-Pad3)") (class "Default")
      (node (ref "IC8") (pin "3") (pinfunction "3_3") (pintype "passive"))
    )
    (net (code "72") (name "unconnected-(IC8-Pad4)") (class "Default")
      (node (ref "IC8") (pin "4") (pinfunction "4_4") (pintype "passive"))
    )
    (net (code "73") (name "unconnected-(IC8-Pad6)") (class "Default")
      (node (ref "IC8") (pin "6") (pinfunction "6_6") (pintype "passive"))
    )
    (net (code "74") (name "unconnected-(IC9-Pad5)") (class "Default")
      (node (ref "IC9") (pin "5") (pinfunction "5_5") (pintype "passive"))
    )
    (net (code "75") (name "unconnected-(IC9-Pad6)") (class "Default")
      (node (ref "IC9") (pin "6") (pinfunction "6_6") (pintype "passive"))
    )
    (net (code "76") (name "unconnected-(IC9-Pad7)") (class "Default")
      (node (ref "IC9") (pin "7") (pinfunction "7_7") (pintype "passive"))
    )
    (net (code "77") (name "unconnected-(QG1-TS-Pad1)") (class "Default")
      (node (ref "QG1") (pin "1") (pinfunction "TS_1") (pintype "passive"))
    )
    (net (code "78") (name "unconnected-(SV2-Pad1)") (class "Default")
      (node (ref "SV2") (pin "1") (pinfunction "1_1") (pintype "passive"))
    )
    (net (code "79") (name "unconnected-(SV2-Pad2)") (class "Default")
      (node (ref "SV2") (pin "2") (pinfunction "2_2") (pintype "passive"))
    )
    (net (code "80") (name "unconnected-(SV2-Pad3)") (class "Default")
      (node (ref "SV2") (pin "3") (pinfunction "3_3") (pintype "passive"))
    )
    (net (code "81") (name "unconnected-(SV4-Pad1)") (class "Default")
      (node (ref "SV4") (pin "1") (pinfunction "1_1") (pintype "passive"))
    )
    (net (code "82") (name "unconnected-(SV4-Pad2)") (class "Default")
      (node (ref "SV4") (pin "2") (pinfunction "2_2") (pintype "passive"))
    )
    (net (code "83") (name "unconnected-(SV4-Pad3)") (class "Default")
      (node (ref "SV4") (pin "3") (pinfunction "3_3") (pintype "passive"))
    )
  )
)
